# 5Vsupply.net
KiCad netlist of a schematic drawn in Altium Designer
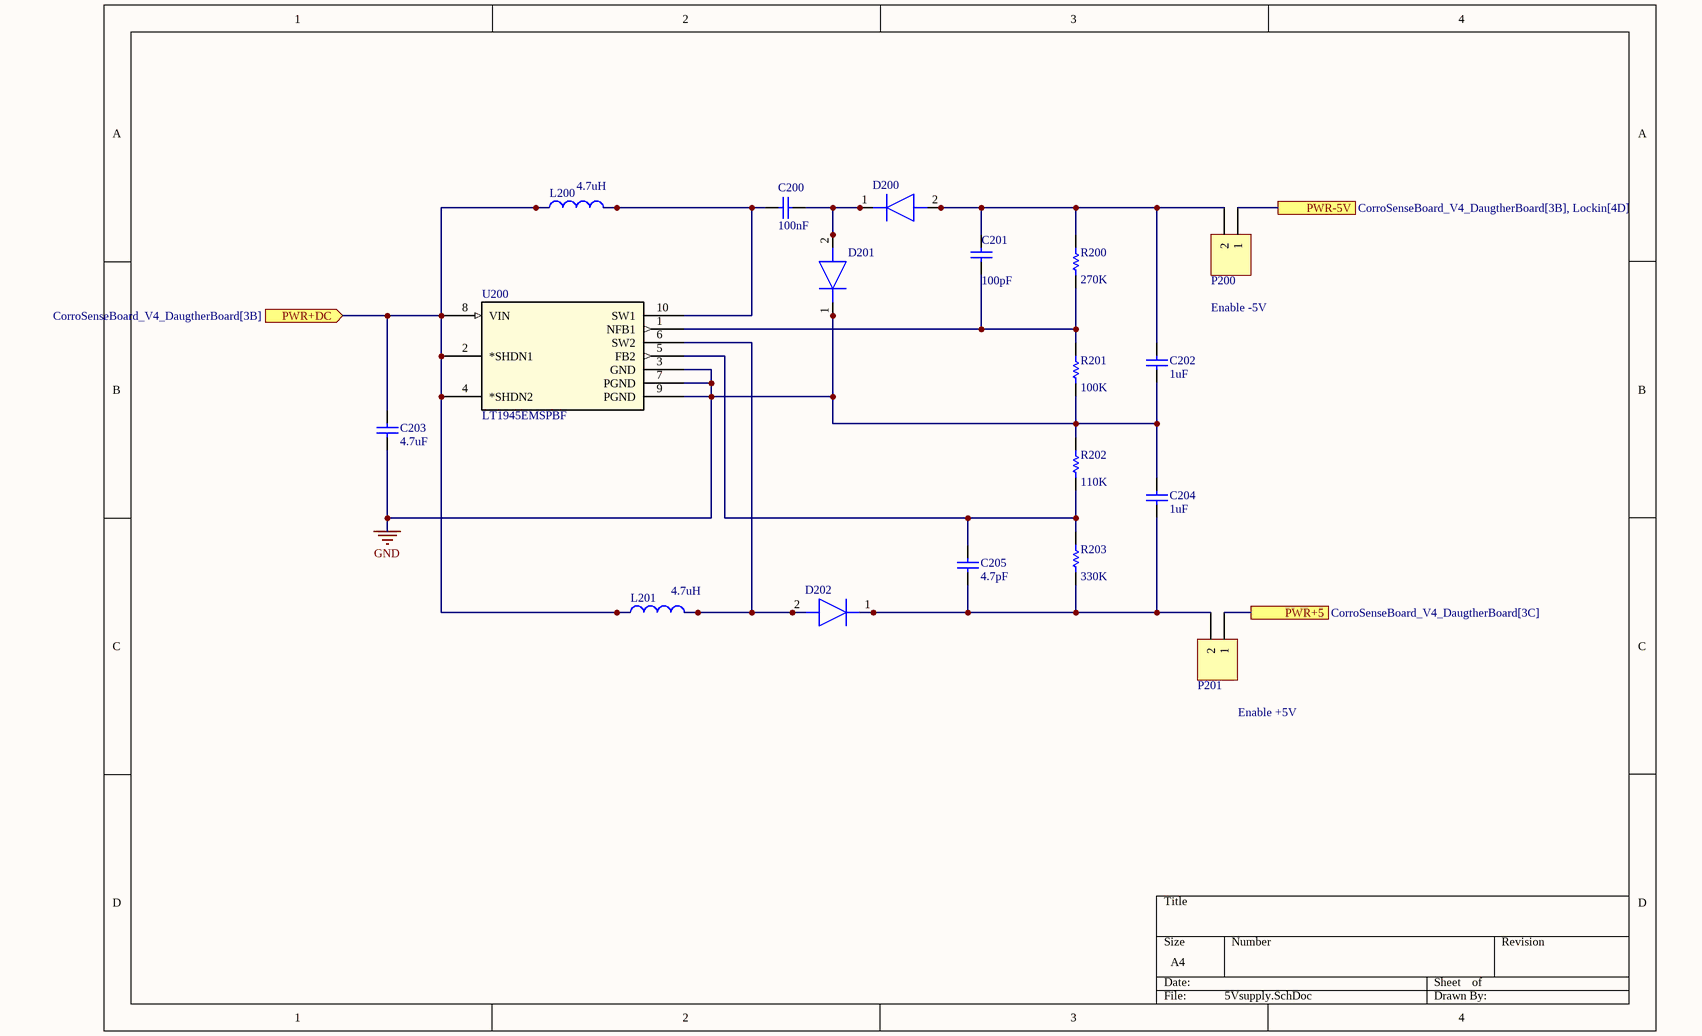
[diagram p0: 5Vsupply.SchDoc]

(export (version "E")
  (design (tool "Eeschema 10.0.6"))
  (components
    (comp (ref "C200")
      (value "100nF")
      (footprint "1608[0603]")
      (description "CAP CER 25V X7R 0603")
      (fields (field (name "TOLERANCE") "±10%") (field (name "MANUFACTURER") "Murata Electronics"))
      (libsource (lib "Miscellaneous Devices") (part "Cap"))
    )
    (comp (ref "C201")
      (value "100pF")
      (footprint "1608[0603]")
      (description "CAP CER 25V X7R 0603")
      (fields (field (name "TOLERANCE") "±10%") (field (name "MANUFACTURER") "KYOCERA AVX"))
      (libsource (lib "Miscellaneous Devices") (part "Cap"))
    )
    (comp (ref "C202")
      (value "1uF")
      (footprint "1608[0603]")
      (description "CAP CER 25V X7R 0603")
      (fields (field (name "TOLERANCE") "±10%") (field (name "MANUFACTURER") "Murata Electronics"))
      (libsource (lib "Miscellaneous Devices") (part "Cap"))
    )
    (comp (ref "C203")
      (value "4.7uF")
      (footprint "1608[0603]")
      (description "CAP CER 25V X7R 0603")
      (fields (field (name "TOLERANCE") "±10%") (field (name "MANUFACTURER") "Murata Electronics"))
      (libsource (lib "Miscellaneous Devices") (part "Cap"))
    )
    (comp (ref "C204")
      (value "1uF")
      (footprint "1608[0603]")
      (description "CAP CER 25V X7R 0603")
      (fields (field (name "TOLERANCE") "±10%") (field (name "MANUFACTURER") "Murata Electronics"))
      (libsource (lib "Miscellaneous Devices") (part "Cap"))
    )
    (comp (ref "C205")
      (value "4.7pF")
      (footprint "1608[0603]")
      (description "CAP CER 25V X7R 0603")
      (fields (field (name "TOLERANCE") "±10%") (field (name "MANUFACTURER") "Murata Electronics"))
      (libsource (lib "Miscellaneous Devices") (part "Cap"))
    )
    (comp (ref "D200")
      (value "ZHCS400TA")
      (footprint "SamacSys:SOD2513X120N")
      (description "Diode")
      (fields
        (field (name "MOUSER PART NUMBER") "522-ZHCS400TA")
        (field (name "MANUFACTURER") "Diodes Incorporated")
      )
      (libsource (lib "*") (part "ZHCS400TA"))
    )
    (comp (ref "D201")
      (value "ZHCS400TA")
      (footprint "SamacSys:SOD2513X120N")
      (description "Diode")
      (fields
        (field (name "MOUSER PART NUMBER") "522-ZHCS400TA")
        (field (name "MANUFACTURER") "Diodes Incorporated")
      )
      (libsource (lib "*") (part "ZHCS400TA"))
    )
    (comp (ref "D202")
      (value "ZHCS400TA")
      (footprint "SamacSys:SOD2513X120N")
      (description "Diode")
      (fields
        (field (name "MOUSER PART NUMBER") "522-ZHCS400TA")
        (field (name "MANUFACTURER") "Diodes Incorporated")
      )
      (libsource (lib "*") (part "ZHCS400TA"))
    )
    (comp (ref "L200")
      (value "4.7uH")
      (footprint "6-0805_N")
      (description "FIXED IND 4.7UH 620MA 550MOHM SM")
      (fields
        (field (name "MANUFACTURER") "Murata Electronics")
        (field (name "MPN") "LQM18PN4R7MFRL")
        (field (name "PUBLISHER") "Altium Limited")
      )
      (libsource (lib "Miscellaneous Devices") (part "Inductor"))
    )
    (comp (ref "L201")
      (value "4.7uH")
      (footprint "6-0805_N")
      (description "FIXED IND 4.7UH 620MA 550MOHM SM")
      (fields
        (field (name "MANUFACTURER") "Murata Electronics")
        (field (name "MPN") "LQM18PN4R7MFRL")
        (field (name "PUBLISHER") "Altium Limited")
      )
      (libsource (lib "Miscellaneous Devices") (part "Inductor"))
    )
    (comp (ref "P200")
      (value "Header, 2-Pin")
      (footprint "HDR1X2")
      (fields
        (field (name "MANUFACTURER") "Wurth Elektronik")
        (field (name "MPN") "61300211121")
        (field (name "PUBLISHER") "Altium Limited")
      )
      (libsource (lib "Miscellaneous Connectors") (part "Header 2"))
    )
    (comp (ref "P201")
      (value "Header, 2-Pin")
      (footprint "HDR1X2")
      (fields
        (field (name "MANUFACTURER") "Wurth Elektronik")
        (field (name "MPN") "61300211121")
        (field (name "PUBLISHER") "Altium Limited")
      )
      (libsource (lib "Miscellaneous Connectors") (part "Header 2"))
    )
    (comp (ref "R200")
      (value "270K")
      (footprint "1608[0603]")
      (description "RES SMD 2% 1.5W 0603")
      (fields
        (field (name "TOLERANCE") "2%")
        (field (name "MANUFACTURER") "YAGEO")
        (field (name "PUBLISHER") "Altium Limited")
      )
      (libsource (lib "Res1") (part "Res1"))
    )
    (comp (ref "R201")
      (value "100K")
      (footprint "1608[0603]")
      (description "RES SMD 2% 1.5W 0603")
      (fields
        (field (name "TOLERANCE") "2%")
        (field (name "MANUFACTURER") "YAGEO")
        (field (name "PUBLISHER") "Altium Limited")
      )
      (libsource (lib "Res1") (part "Res1"))
    )
    (comp (ref "R202")
      (value "110K")
      (footprint "1608[0603]")
      (description "RES SMD 2% 1.5W 0603")
      (fields
        (field (name "TOLERANCE") "2%")
        (field (name "MANUFACTURER") "YAGEO")
        (field (name "PUBLISHER") "Altium Limited")
      )
      (libsource (lib "Res1") (part "Res1"))
    )
    (comp (ref "R203")
      (value "330K")
      (footprint "1608[0603]")
      (description "RES SMD 2% 1.5W 0603")
      (fields
        (field (name "TOLERANCE") "2%")
        (field (name "MANUFACTURER") "YAGEO")
        (field (name "PUBLISHER") "Altium Limited")
      )
      (libsource (lib "Res1") (part "Res1"))
    )
    (comp (ref "U200")
      (value "LT1945EMSPBF")
      (footprint "MSOP-10_MS_LIT")
      (description "No Description Available")
      (fields (field (name "MANUFACTURER") "Analog Devices Inc"))
      (libsource (lib "CorrosenseBoard_V4.2") (part "LT1945EMSPBF"))
    )
  )
  (nets
    (net (code "1") (name "/PWR+5") (class "Default")
      (node (ref "P201") (pin "1") (pinfunction "1_1") (pintype "passive"))
    )
    (net (code "2") (name "/PWR+DC") (class "Default")
      (node (ref "C203") (pin "1") (pinfunction "1_1") (pintype "passive"))
      (node (ref "L200") (pin "1") (pinfunction "1_1") (pintype "passive"))
      (node (ref "L201") (pin "1") (pinfunction "1_1") (pintype "passive"))
      (node (ref "U200") (pin "2") (pinfunction "*SHDN1_2") (pintype "passive"))
      (node (ref "U200") (pin "4") (pinfunction "*SHDN2_4") (pintype "passive"))
      (node (ref "U200") (pin "8") (pinfunction "VIN_8") (pintype "input"))
    )
    (net (code "3") (name "/PWR-5V") (class "Default")
      (node (ref "P200") (pin "1") (pinfunction "1_1") (pintype "passive"))
    )
    (net (code "4") (name "GND") (class "Default")
      (node (ref "C202") (pin "2") (pinfunction "2_2") (pintype "passive"))
      (node (ref "C203") (pin "2") (pinfunction "2_2") (pintype "passive"))
      (node (ref "C204") (pin "1") (pinfunction "1_1") (pintype "passive"))
      (node (ref "D201") (pin "1") (pinfunction "K_1") (pintype "passive"))
      (node (ref "R201") (pin "1") (pinfunction "1_1") (pintype "passive"))
      (node (ref "R202") (pin "2") (pinfunction "2_2") (pintype "passive"))
      (node (ref "U200") (pin "3") (pinfunction "GND_3") (pintype "power_in"))
      (node (ref "U200") (pin "7") (pinfunction "PGND_7") (pintype "power_in"))
      (node (ref "U200") (pin "9") (pinfunction "PGND_9") (pintype "power_in"))
    )
    (net (code "5") (name "Net-(D200-A)") (class "Default")
      (node (ref "C201") (pin "2") (pinfunction "2_2") (pintype "passive"))
      (node (ref "C202") (pin "1") (pinfunction "1_1") (pintype "passive"))
      (node (ref "D200") (pin "2") (pinfunction "A_2") (pintype "passive"))
      (node (ref "P200") (pin "2") (pinfunction "2_2") (pintype "passive"))
      (node (ref "R200") (pin "2") (pinfunction "2_2") (pintype "passive"))
    )
    (net (code "6") (name "Net-(D200-K)") (class "Default")
      (node (ref "C200") (pin "1") (pinfunction "1_1") (pintype "passive"))
      (node (ref "D200") (pin "1") (pinfunction "K_1") (pintype "passive"))
      (node (ref "D201") (pin "2") (pinfunction "A_2") (pintype "passive"))
    )
    (net (code "7") (name "Net-(D202-A)") (class "Default")
      (node (ref "D202") (pin "2") (pinfunction "A_2") (pintype "passive"))
      (node (ref "L201") (pin "2") (pinfunction "2_2") (pintype "passive"))
      (node (ref "U200") (pin "6") (pinfunction "SW2_6") (pintype "passive"))
    )
    (net (code "8") (name "Net-(D202-K)") (class "Default")
      (node (ref "C204") (pin "2") (pinfunction "2_2") (pintype "passive"))
      (node (ref "C205") (pin "2") (pinfunction "2_2") (pintype "passive"))
      (node (ref "D202") (pin "1") (pinfunction "K_1") (pintype "passive"))
      (node (ref "P201") (pin "2") (pinfunction "2_2") (pintype "passive"))
      (node (ref "R203") (pin "1") (pinfunction "1_1") (pintype "passive"))
    )
    (net (code "9") (name "Net-(U200-FB2)") (class "Default")
      (node (ref "C205") (pin "1") (pinfunction "1_1") (pintype "passive"))
      (node (ref "R202") (pin "1") (pinfunction "1_1") (pintype "passive"))
      (node (ref "R203") (pin "2") (pinfunction "2_2") (pintype "passive"))
      (node (ref "U200") (pin "5") (pinfunction "FB2_5") (pintype "output"))
    )
    (net (code "10") (name "Net-(U200-NFB1)") (class "Default")
      (node (ref "C201") (pin "1") (pinfunction "1_1") (pintype "passive"))
      (node (ref "R200") (pin "1") (pinfunction "1_1") (pintype "passive"))
      (node (ref "R201") (pin "2") (pinfunction "2_2") (pintype "passive"))
      (node (ref "U200") (pin "1") (pinfunction "NFB1_1") (pintype "output"))
    )
    (net (code "11") (name "Net-(U200-SW1)") (class "Default")
      (node (ref "C200") (pin "2") (pinfunction "2_2") (pintype "passive"))
      (node (ref "L200") (pin "2") (pinfunction "2_2") (pintype "passive"))
      (node (ref "U200") (pin "10") (pinfunction "SW1_10") (pintype "passive"))
    )
  )
)
